# SSTuino_Evo.net
KiCad netlist of a schematic drawn in EAGLE
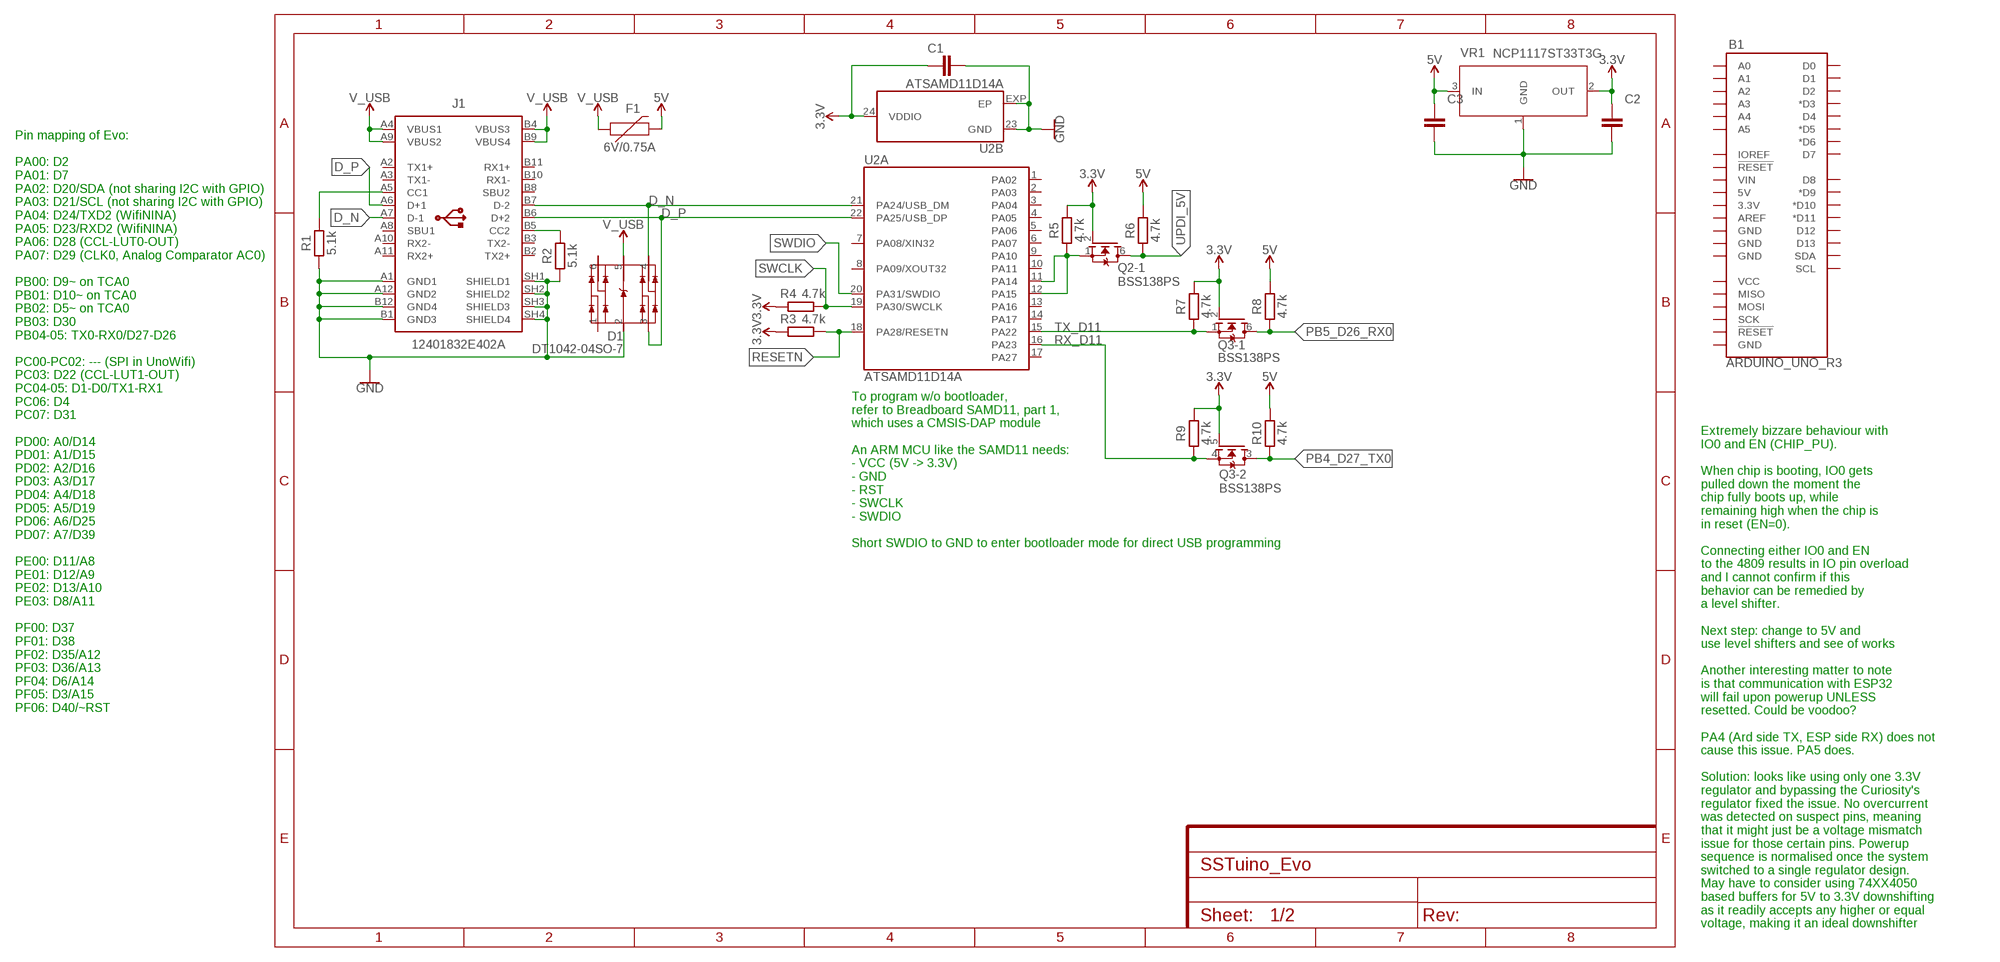
[diagram p0: schematic, sheet 1]
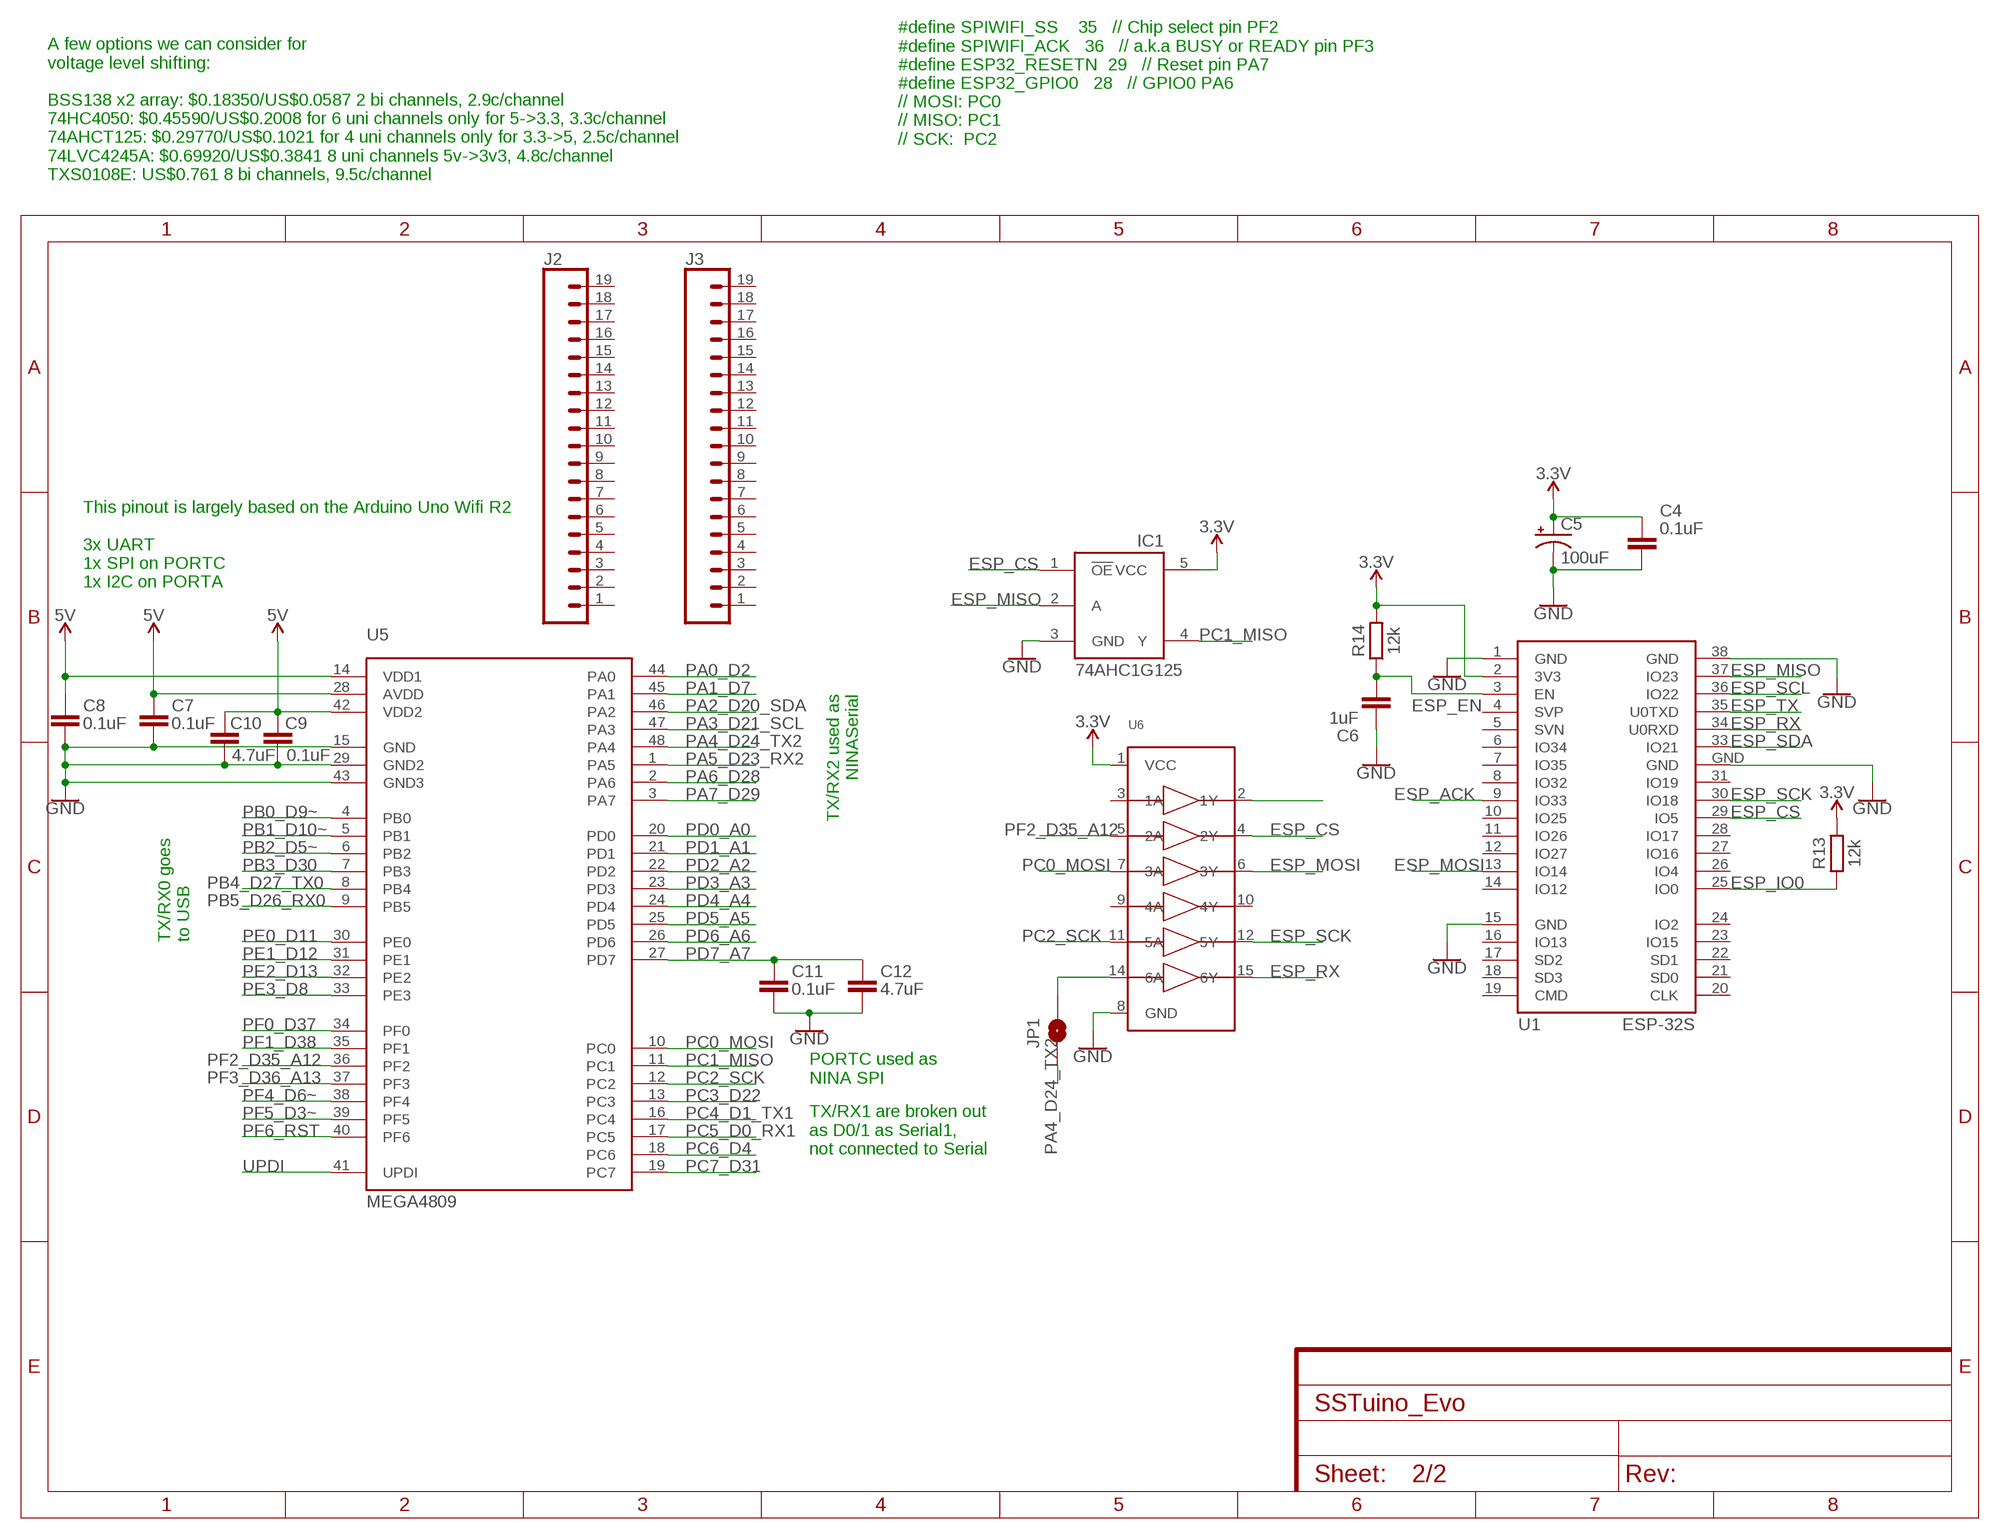
[diagram p1: schematic, sheet 2]

(export (version "E")
  (design (tool "Eeschema 10.0.6"))
  (components
    (comp (ref "C4")
      (value "0.1uF")
      (footprint "eagle-import:CAPC1005X60")
      (libsource (lib "eagle-import") (part "CCHIP-0402(1005-METRIC)_"))
    )
    (comp (ref "C5")
      (value "100uF")
      (footprint "eagle-import:CAPMP3216X180N")
      (libsource (lib "eagle-import") (part "C-POL-USTANTALUM-1206(3216-METRIC)_"))
    )
    (comp (ref "C6")
      (value "1uF")
      (footprint "eagle-import:CAPC1005X60")
      (libsource (lib "eagle-import") (part "CCHIP-0402(1005-METRIC)_"))
    )
    (comp (ref "C7")
      (value "0.1uF")
      (footprint "eagle-import:CAPC1005X60")
      (libsource (lib "eagle-import") (part "CCHIP-0402(1005-METRIC)_"))
    )
    (comp (ref "C8")
      (value "0.1uF")
      (footprint "eagle-import:CAPC1005X60")
      (libsource (lib "eagle-import") (part "CCHIP-0402(1005-METRIC)_"))
    )
    (comp (ref "C9")
      (value "0.1uF")
      (footprint "eagle-import:CAPC1005X60")
      (libsource (lib "eagle-import") (part "CCHIP-0402(1005-METRIC)_"))
    )
    (comp (ref "C10")
      (value "4.7uF")
      (footprint "eagle-import:CAPC1005X60")
      (libsource (lib "eagle-import") (part "CCHIP-0402(1005-METRIC)_"))
    )
    (comp (ref "C11")
      (value "0.1uF")
      (footprint "eagle-import:CAPC1005X60")
      (libsource (lib "eagle-import") (part "CCHIP-0402(1005-METRIC)_"))
    )
    (comp (ref "C12")
      (value "4.7uF")
      (footprint "eagle-import:CAPC1005X60")
      (libsource (lib "eagle-import") (part "CCHIP-0402(1005-METRIC)_"))
    )
    (comp (ref "IC1")
      (value "74AHC1G125")
      (footprint "eagle-import:SOT23-5L")
      (libsource (lib "eagle-import") (part "74AHC1G125"))
    )
    (comp (ref "J2")
      (value "CONN_191X19_NO_SILK")
      (footprint "eagle-import:1X19_NO_SILK")
      (libsource (lib "eagle-import") (part "CONN_191X19_NO_SILK"))
    )
    (comp (ref "J3")
      (value "CONN_191X19_NO_SILK")
      (footprint "eagle-import:1X19_NO_SILK")
      (libsource (lib "eagle-import") (part "CONN_191X19_NO_SILK"))
    )
    (comp (ref "JP1")
      (value "JUMPER-SMT_2_NO_SILK")
      (footprint "eagle-import:SMT-JUMPER_2_NO_SILK")
      (libsource (lib "eagle-import") (part "JUMPER-SMT_2_NO_SILK"))
    )
    (comp (ref "R13")
      (value "12k")
      (footprint "eagle-import:RESC1005X40")
      (libsource (lib "eagle-import") (part "RCHIP-0402(1005-METRIC)_"))
    )
    (comp (ref "R14")
      (value "12k")
      (footprint "eagle-import:RESC1005X40")
      (libsource (lib "eagle-import") (part "RCHIP-0402(1005-METRIC)_"))
    )
    (comp (ref "U1")
      (value "ESP-32S")
      (footprint "eagle-import:ESP-32S")
      (libsource (lib "eagle-import") (part "ESP-32S"))
    )
    (comp (ref "U5")
      (value "MEGA4809")
      (footprint "eagle-import:TQFP48")
      (libsource (lib "eagle-import") (part "MEGA4809"))
    )
    (comp (ref "U6")
      (value "74HC4050DTSSOP")
      (footprint "eagle-import:TSSOP16")
      (libsource (lib "eagle-import") (part "74HC4050DTSSOP"))
    )
    (comp (ref "B1")
      (value "ARDUINO_UNO_R3")
      (footprint "eagle-import:ARDUINO_R3")
      (libsource (lib "eagle-import") (part "ARDUINO_UNO_R3"))
    )
    (comp (ref "C1")
      (value "100n")
      (footprint "eagle-import:CAPC1005X60")
      (libsource (lib "eagle-import") (part "CCHIP-0402(1005-METRIC)_"))
    )
    (comp (ref "C2")
      (value "10uF")
      (footprint "eagle-import:CAPC1608X85")
      (libsource (lib "eagle-import") (part "CCHIP-0603(1608-METRIC)_"))
    )
    (comp (ref "C3")
      (value "10uF")
      (footprint "eagle-import:CAPC1608X85")
      (libsource (lib "eagle-import") (part "CCHIP-0603(1608-METRIC)_"))
    )
    (comp (ref "D1")
      (value "DT1042-04SO-7")
      (footprint "eagle-import:SOT95P285X140-6N")
      (fields (field (name "DIGI-KEY_PART_NUMBER") "DT1042-04SO-7DICT-ND") (field (name "MF") "Diodes Inc."))
      (libsource (lib "eagle-import") (part "DT1042-04SO-7"))
    )
    (comp (ref "F1")
      (value "6V/0.75A")
      (footprint "eagle-import:1206")
      (libsource (lib "eagle-import") (part "PPTC_THREE-QUARTER-AMP"))
    )
    (comp (ref "J1")
      (value "12401832E402A")
      (footprint "eagle-import:12401832E402A")
      (fields (field (name "MANUFACTURER") "Amphenol ICC"))
      (libsource (lib "eagle-import") (part "12401832E402A"))
    )
    (comp (ref "Q2")
      (value "BSS138PS")
      (footprint "eagle-import:ARDUINO-TRANSISTORS_SOT363")
      (fields (field (name "MANUFACTURER") "NXP"))
      (libsource (lib "eagle-import") (part "BSS138PS"))
    )
    (comp (ref "Q3")
      (value "BSS138PS")
      (footprint "eagle-import:ARDUINO-TRANSISTORS_SOT363")
      (fields (field (name "MANUFACTURER") "NXP"))
      (libsource (lib "eagle-import") (part "BSS138PS"))
    )
    (comp (ref "R1")
      (value "5.1k")
      (footprint "eagle-import:RESC1005X40")
      (libsource (lib "eagle-import") (part "RCHIP-0402(1005-METRIC)_"))
    )
    (comp (ref "R2")
      (value "5.1k")
      (footprint "eagle-import:RESC1005X40")
      (libsource (lib "eagle-import") (part "RCHIP-0402(1005-METRIC)_"))
    )
    (comp (ref "R3")
      (value "4.7k")
      (footprint "eagle-import:RESC1005X40")
      (libsource (lib "eagle-import") (part "RCHIP-0402(1005-METRIC)_"))
    )
    (comp (ref "R4")
      (value "4.7k")
      (footprint "eagle-import:RESC1005X40")
      (libsource (lib "eagle-import") (part "RCHIP-0402(1005-METRIC)_"))
    )
    (comp (ref "R5")
      (value "4.7k")
      (footprint "eagle-import:RESC1005X40")
      (libsource (lib "eagle-import") (part "RCHIP-0402(1005-METRIC)_"))
    )
    (comp (ref "R6")
      (value "4.7k")
      (footprint "eagle-import:RESC1005X40")
      (libsource (lib "eagle-import") (part "RCHIP-0402(1005-METRIC)_"))
    )
    (comp (ref "R7")
      (value "4.7k")
      (footprint "eagle-import:RESC1005X40")
      (libsource (lib "eagle-import") (part "RCHIP-0402(1005-METRIC)_"))
    )
    (comp (ref "R8")
      (value "4.7k")
      (footprint "eagle-import:RESC1005X40")
      (libsource (lib "eagle-import") (part "RCHIP-0402(1005-METRIC)_"))
    )
    (comp (ref "R9")
      (value "4.7k")
      (footprint "eagle-import:RESC1005X40")
      (libsource (lib "eagle-import") (part "RCHIP-0402(1005-METRIC)_"))
    )
    (comp (ref "R10")
      (value "4.7k")
      (footprint "eagle-import:RESC1005X40")
      (libsource (lib "eagle-import") (part "RCHIP-0402(1005-METRIC)_"))
    )
    (comp (ref "U2")
      (value "ATSAMD11D14A")
      (footprint "eagle-import:ARDUINO-UCS&SOCS_HVQFN24")
      (fields (field (name "MANUFACTURER") "Microchip"))
      (libsource (lib "eagle-import") (part "ATSAMD11D14"))
    )
    (comp (ref "VR1")
      (value "NCP1117ST33T3G")
      (footprint "eagle-import:SOT230P700X170-4")
      (fields (field (name "MANUFACTURER") "ON Semiconductor"))
      (libsource (lib "eagle-import") (part "NCP1117ST33T3GSOT-223"))
    )
  )
  (nets
    (net (code "1") (name "3.3V") (class "Default")
      (node (ref "C1") (pin "1") (pinfunction "1_1") (pintype "passive"))
      (node (ref "C2") (pin "1") (pinfunction "1_1") (pintype "passive"))
      (node (ref "C4") (pin "1") (pinfunction "1_1") (pintype "passive"))
      (node (ref "C5") (pin "1") (pinfunction "+_1") (pintype "passive"))
      (node (ref "IC1") (pin "5") (pinfunction "VCC_5") (pintype "power_in"))
      (node (ref "Q2") (pin "2") (pinfunction "G_2") (pintype "passive"))
      (node (ref "Q3") (pin "2") (pinfunction "G_2") (pintype "passive"))
      (node (ref "Q3") (pin "5") (pinfunction "G_5") (pintype "passive"))
      (node (ref "R13") (pin "2") (pinfunction "2_2") (pintype "passive"))
      (node (ref "R14") (pin "2") (pinfunction "2_2") (pintype "passive"))
      (node (ref "R3") (pin "2") (pinfunction "2_2") (pintype "passive"))
      (node (ref "R4") (pin "2") (pinfunction "2_2") (pintype "passive"))
      (node (ref "R5") (pin "2") (pinfunction "2_2") (pintype "passive"))
      (node (ref "R7") (pin "2") (pinfunction "2_2") (pintype "passive"))
      (node (ref "R9") (pin "2") (pinfunction "2_2") (pintype "passive"))
      (node (ref "U1") (pin "2") (pinfunction "3V3_2") (pintype "power_in"))
      (node (ref "U2") (pin "24") (pinfunction "VDDIO_24") (pintype "power_in"))
      (node (ref "U6") (pin "1") (pinfunction "VCC_1") (pintype "bidirectional"))
      (node (ref "VR1") (pin "2") (pinfunction "OUT_2") (pintype "output"))
    )
    (net (code "2") (name "5V") (class "Default")
      (node (ref "C10") (pin "1") (pinfunction "1_1") (pintype "passive"))
      (node (ref "C3") (pin "1") (pinfunction "1_1") (pintype "passive"))
      (node (ref "C7") (pin "1") (pinfunction "1_1") (pintype "passive"))
      (node (ref "C8") (pin "1") (pinfunction "1_1") (pintype "passive"))
      (node (ref "C9") (pin "1") (pinfunction "1_1") (pintype "passive"))
      (node (ref "F1") (pin "2") (pinfunction "2_2") (pintype "bidirectional"))
      (node (ref "R10") (pin "2") (pinfunction "2_2") (pintype "passive"))
      (node (ref "R6") (pin "2") (pinfunction "2_2") (pintype "passive"))
      (node (ref "R8") (pin "2") (pinfunction "2_2") (pintype "passive"))
      (node (ref "U5") (pin "14") (pinfunction "VDD1_14") (pintype "bidirectional"))
      (node (ref "U5") (pin "28") (pinfunction "AVDD_28") (pintype "bidirectional"))
      (node (ref "U5") (pin "42") (pinfunction "VDD2_42") (pintype "bidirectional"))
      (node (ref "VR1") (pin "3") (pinfunction "IN_3") (pintype "input"))
    )
    (net (code "3") (name "D_N") (class "Default")
      (node (ref "D1") (pin "4") (pinfunction "IO3_4") (pintype "passive"))
      (node (ref "J1") (pin "A7") (pinfunction "D-1_A7") (pintype "bidirectional"))
      (node (ref "J1") (pin "B7") (pinfunction "D-2_B7") (pintype "bidirectional"))
      (node (ref "U2") (pin "21") (pinfunction "PA24/USB_DM_21") (pintype "bidirectional"))
    )
    (net (code "4") (name "D_P") (class "Default")
      (node (ref "D1") (pin "3") (pinfunction "IO2_3") (pintype "passive"))
      (node (ref "J1") (pin "A6") (pinfunction "D+1_A6") (pintype "bidirectional"))
      (node (ref "J1") (pin "B6") (pinfunction "D+2_B6") (pintype "bidirectional"))
      (node (ref "U2") (pin "22") (pinfunction "PA25/USB_DP_22") (pintype "bidirectional"))
    )
    (net (code "5") (name "ESP_ACK") (class "Default")
      (node (ref "U1") (pin "9") (pinfunction "IO33_9") (pintype "bidirectional"))
    )
    (net (code "6") (name "ESP_CS") (class "Default")
      (node (ref "IC1") (pin "1") (pinfunction "~{OE}_1") (pintype "input"))
      (node (ref "U1") (pin "29") (pinfunction "IO5_29") (pintype "bidirectional"))
      (node (ref "U6") (pin "4") (pinfunction "2Y_4") (pintype "bidirectional"))
    )
    (net (code "7") (name "ESP_EN") (class "Default")
      (node (ref "C6") (pin "2") (pinfunction "2_2") (pintype "passive"))
      (node (ref "R14") (pin "1") (pinfunction "1_1") (pintype "passive"))
      (node (ref "U1") (pin "3") (pinfunction "EN_3") (pintype "input"))
    )
    (net (code "8") (name "ESP_IO0") (class "Default")
      (node (ref "R13") (pin "1") (pinfunction "1_1") (pintype "passive"))
      (node (ref "U1") (pin "25") (pinfunction "IO0_25") (pintype "bidirectional"))
    )
    (net (code "9") (name "ESP_MISO") (class "Default")
      (node (ref "IC1") (pin "2") (pinfunction "A_2") (pintype "input"))
      (node (ref "U1") (pin "37") (pinfunction "IO23_37") (pintype "bidirectional"))
    )
    (net (code "10") (name "ESP_MOSI") (class "Default")
      (node (ref "U1") (pin "13") (pinfunction "IO14_13") (pintype "bidirectional"))
      (node (ref "U6") (pin "6") (pinfunction "3Y_6") (pintype "bidirectional"))
    )
    (net (code "11") (name "ESP_RX") (class "Default")
      (node (ref "U1") (pin "34") (pinfunction "U0RXD_34") (pintype "bidirectional"))
      (node (ref "U6") (pin "15") (pinfunction "6Y_15") (pintype "bidirectional"))
    )
    (net (code "12") (name "ESP_SCK") (class "Default")
      (node (ref "U1") (pin "30") (pinfunction "IO18_30") (pintype "bidirectional"))
      (node (ref "U6") (pin "12") (pinfunction "5Y_12") (pintype "bidirectional"))
    )
    (net (code "13") (name "ESP_SCL") (class "Default")
      (node (ref "U1") (pin "36") (pinfunction "IO22_36") (pintype "bidirectional"))
    )
    (net (code "14") (name "ESP_SDA") (class "Default")
      (node (ref "U1") (pin "33") (pinfunction "IO21_33") (pintype "bidirectional"))
    )
    (net (code "15") (name "ESP_TX") (class "Default")
      (node (ref "U1") (pin "35") (pinfunction "U0TXD_35") (pintype "bidirectional"))
    )
    (net (code "16") (name "GND") (class "Default")
      (node (ref "C1") (pin "2") (pinfunction "2_2") (pintype "passive"))
      (node (ref "C10") (pin "2") (pinfunction "2_2") (pintype "passive"))
      (node (ref "C11") (pin "2") (pinfunction "2_2") (pintype "passive"))
      (node (ref "C12") (pin "2") (pinfunction "2_2") (pintype "passive"))
      (node (ref "C2") (pin "2") (pinfunction "2_2") (pintype "passive"))
      (node (ref "C3") (pin "2") (pinfunction "2_2") (pintype "passive"))
      (node (ref "C4") (pin "2") (pinfunction "2_2") (pintype "passive"))
      (node (ref "C5") (pin "2") (pinfunction "-_2") (pintype "passive"))
      (node (ref "C6") (pin "1") (pinfunction "1_1") (pintype "passive"))
      (node (ref "C7") (pin "2") (pinfunction "2_2") (pintype "passive"))
      (node (ref "C8") (pin "2") (pinfunction "2_2") (pintype "passive"))
      (node (ref "C9") (pin "2") (pinfunction "2_2") (pintype "passive"))
      (node (ref "D1") (pin "2") (pinfunction "VSS_2") (pintype "power_in"))
      (node (ref "IC1") (pin "3") (pinfunction "GND_3") (pintype "power_in"))
      (node (ref "J1") (pin "A1") (pinfunction "GND1_A1") (pintype "power_in"))
      (node (ref "J1") (pin "A12") (pinfunction "GND2_A12") (pintype "power_in"))
      (node (ref "J1") (pin "B1") (pinfunction "GND3_B1") (pintype "power_in"))
      (node (ref "J1") (pin "B12") (pinfunction "GND4_B12") (pintype "power_in"))
      (node (ref "J1") (pin "SH1") (pinfunction "SHIELD1_SH1") (pintype "power_in"))
      (node (ref "J1") (pin "SH2") (pinfunction "SHIELD2_SH2") (pintype "power_in"))
      (node (ref "J1") (pin "SH3") (pinfunction "SHIELD3_SH3") (pintype "power_in"))
      (node (ref "J1") (pin "SH4") (pinfunction "SHIELD4_SH4") (pintype "power_in"))
      (node (ref "R1") (pin "1") (pinfunction "1_1") (pintype "passive"))
      (node (ref "R2") (pin "1") (pinfunction "1_1") (pintype "passive"))
      (node (ref "U1") (pin "1") (pinfunction "GND_1") (pintype "power_in"))
      (node (ref "U1") (pin "15") (pinfunction "GND_15") (pintype "power_in"))
      (node (ref "U1") (pin "38") (pinfunction "GND_38") (pintype "power_in"))
      (node (ref "U1") (pin "GND") (pinfunction "GND_GND") (pintype "power_in"))
      (node (ref "U2") (pin "23") (pinfunction "GND_23") (pintype "power_in"))
      (node (ref "U2") (pin "EXP") (pinfunction "EP_EXP") (pintype "power_in"))
      (node (ref "U5") (pin "15") (pinfunction "GND_15") (pintype "bidirectional"))
      (node (ref "U5") (pin "29") (pinfunction "GND2_29") (pintype "bidirectional"))
      (node (ref "U5") (pin "43") (pinfunction "GND3_43") (pintype "bidirectional"))
      (node (ref "U6") (pin "8") (pinfunction "GND_8") (pintype "bidirectional"))
      (node (ref "VR1") (pin "1") (pinfunction "GND_1") (pintype "passive"))
    )
    (net (code "17") (name "Net-(J1-CC1)") (class "Default")
      (node (ref "J1") (pin "A5") (pinfunction "CC1_A5") (pintype "bidirectional"))
      (node (ref "R1") (pin "2") (pinfunction "2_2") (pintype "passive"))
    )
    (net (code "18") (name "Net-(J1-CC2)") (class "Default")
      (node (ref "J1") (pin "B5") (pinfunction "CC2_B5") (pintype "bidirectional"))
      (node (ref "R2") (pin "2") (pinfunction "2_2") (pintype "passive"))
    )
    (net (code "19") (name "Net-(Q2A-S)") (class "Default")
      (node (ref "Q2") (pin "1") (pinfunction "S_1") (pintype "passive"))
      (node (ref "R5") (pin "1") (pinfunction "1_1") (pintype "passive"))
      (node (ref "U2") (pin "11") (pinfunction "PA14_11") (pintype "bidirectional"))
      (node (ref "U2") (pin "12") (pinfunction "PA15_12") (pintype "bidirectional"))
    )
    (net (code "20") (name "Net-(U6-6A)") (class "Default")
      (node (ref "JP1") (pin "2") (pinfunction "2_2") (pintype "passive"))
      (node (ref "U6") (pin "14") (pinfunction "6A_14") (pintype "bidirectional"))
    )
    (net (code "21") (name "PA0_D2") (class "Default")
      (node (ref "U5") (pin "44") (pinfunction "PA0_44") (pintype "bidirectional"))
    )
    (net (code "22") (name "PA1_D7") (class "Default")
      (node (ref "U5") (pin "45") (pinfunction "PA1_45") (pintype "bidirectional"))
    )
    (net (code "23") (name "PA2_D20_SDA") (class "Default")
      (node (ref "U5") (pin "46") (pinfunction "PA2_46") (pintype "bidirectional"))
    )
    (net (code "24") (name "PA3_D21_SCL") (class "Default")
      (node (ref "U5") (pin "47") (pinfunction "PA3_47") (pintype "bidirectional"))
    )
    (net (code "25") (name "PA4_D24_TX2") (class "Default")
      (node (ref "JP1") (pin "1") (pinfunction "1_1") (pintype "passive"))
      (node (ref "U5") (pin "48") (pinfunction "PA4_48") (pintype "bidirectional"))
    )
    (net (code "26") (name "PA5_D23_RX2") (class "Default")
      (node (ref "U5") (pin "1") (pinfunction "PA5_1") (pintype "bidirectional"))
    )
    (net (code "27") (name "PA6_D28") (class "Default")
      (node (ref "U5") (pin "2") (pinfunction "PA6_2") (pintype "bidirectional"))
    )
    (net (code "28") (name "PA7_D29") (class "Default")
      (node (ref "U5") (pin "3") (pinfunction "PA7_3") (pintype "bidirectional"))
    )
    (net (code "29") (name "PB0_D9~{}") (class "Default")
      (node (ref "U5") (pin "4") (pinfunction "PB0_4") (pintype "bidirectional"))
    )
    (net (code "30") (name "PB1_D10~{}") (class "Default")
      (node (ref "U5") (pin "5") (pinfunction "PB1_5") (pintype "bidirectional"))
    )
    (net (code "31") (name "PB2_D5~{}") (class "Default")
      (node (ref "U5") (pin "6") (pinfunction "PB2_6") (pintype "bidirectional"))
    )
    (net (code "32") (name "PB3_D30") (class "Default")
      (node (ref "U5") (pin "7") (pinfunction "PB3_7") (pintype "bidirectional"))
    )
    (net (code "33") (name "PB4_D27_TX0") (class "Default")
      (node (ref "Q3") (pin "3") (pinfunction "D_3") (pintype "passive"))
      (node (ref "R10") (pin "1") (pinfunction "1_1") (pintype "passive"))
      (node (ref "U5") (pin "8") (pinfunction "PB4_8") (pintype "bidirectional"))
    )
    (net (code "34") (name "PB5_D26_RX0") (class "Default")
      (node (ref "Q3") (pin "6") (pinfunction "D_6") (pintype "passive"))
      (node (ref "R8") (pin "1") (pinfunction "1_1") (pintype "passive"))
      (node (ref "U5") (pin "9") (pinfunction "PB5_9") (pintype "bidirectional"))
    )
    (net (code "35") (name "PC0_MOSI") (class "Default")
      (node (ref "U5") (pin "10") (pinfunction "PC0_10") (pintype "bidirectional"))
      (node (ref "U6") (pin "7") (pinfunction "3A_7") (pintype "bidirectional"))
    )
    (net (code "36") (name "PC1_MISO") (class "Default")
      (node (ref "IC1") (pin "4") (pinfunction "Y_4") (pintype "output"))
      (node (ref "U5") (pin "11") (pinfunction "PC1_11") (pintype "bidirectional"))
    )
    (net (code "37") (name "PC2_SCK") (class "Default")
      (node (ref "U5") (pin "12") (pinfunction "PC2_12") (pintype "bidirectional"))
      (node (ref "U6") (pin "11") (pinfunction "5A_11") (pintype "bidirectional"))
    )
    (net (code "38") (name "PC3_D22") (class "Default")
      (node (ref "U5") (pin "13") (pinfunction "PC3_13") (pintype "bidirectional"))
    )
    (net (code "39") (name "PC4_D1_TX1") (class "Default")
      (node (ref "U5") (pin "16") (pinfunction "PC4_16") (pintype "bidirectional"))
    )
    (net (code "40") (name "PC5_D0_RX1") (class "Default")
      (node (ref "U5") (pin "17") (pinfunction "PC5_17") (pintype "bidirectional"))
    )
    (net (code "41") (name "PC6_D4") (class "Default")
      (node (ref "U5") (pin "18") (pinfunction "PC6_18") (pintype "bidirectional"))
    )
    (net (code "42") (name "PC7_D31") (class "Default")
      (node (ref "U5") (pin "19") (pinfunction "PC7_19") (pintype "bidirectional"))
    )
    (net (code "43") (name "PD0_A0") (class "Default")
      (node (ref "U5") (pin "20") (pinfunction "PD0_20") (pintype "bidirectional"))
    )
    (net (code "44") (name "PD1_A1") (class "Default")
      (node (ref "U5") (pin "21") (pinfunction "PD1_21") (pintype "bidirectional"))
    )
    (net (code "45") (name "PD2_A2") (class "Default")
      (node (ref "U5") (pin "22") (pinfunction "PD2_22") (pintype "bidirectional"))
    )
    (net (code "46") (name "PD3_A3") (class "Default")
      (node (ref "U5") (pin "23") (pinfunction "PD3_23") (pintype "bidirectional"))
    )
    (net (code "47") (name "PD4_A4") (class "Default")
      (node (ref "U5") (pin "24") (pinfunction "PD4_24") (pintype "bidirectional"))
    )
    (net (code "48") (name "PD5_A5") (class "Default")
      (node (ref "U5") (pin "25") (pinfunction "PD5_25") (pintype "bidirectional"))
    )
    (net (code "49") (name "PD6_A6") (class "Default")
      (node (ref "U5") (pin "26") (pinfunction "PD6_26") (pintype "bidirectional"))
    )
    (net (code "50") (name "PD7_A7") (class "Default")
      (node (ref "C11") (pin "1") (pinfunction "1_1") (pintype "passive"))
      (node (ref "C12") (pin "1") (pinfunction "1_1") (pintype "passive"))
      (node (ref "U5") (pin "27") (pinfunction "PD7_27") (pintype "bidirectional"))
    )
    (net (code "51") (name "PE0_D11") (class "Default")
      (node (ref "U5") (pin "30") (pinfunction "PE0_30") (pintype "bidirectional"))
    )
    (net (code "52") (name "PE1_D12") (class "Default")
      (node (ref "U5") (pin "31") (pinfunction "PE1_31") (pintype "bidirectional"))
    )
    (net (code "53") (name "PE2_D13") (class "Default")
      (node (ref "U5") (pin "32") (pinfunction "PE2_32") (pintype "bidirectional"))
    )
    (net (code "54") (name "PE3_D8") (class "Default")
      (node (ref "U5") (pin "33") (pinfunction "PE3_33") (pintype "bidirectional"))
    )
    (net (code "55") (name "PF0_D37") (class "Default")
      (node (ref "U5") (pin "34") (pinfunction "PF0_34") (pintype "bidirectional"))
    )
    (net (code "56") (name "PF1_D38") (class "Default")
      (node (ref "U5") (pin "35") (pinfunction "PF1_35") (pintype "bidirectional"))
    )
    (net (code "57") (name "PF2_D35_A12") (class "Default")
      (node (ref "U5") (pin "36") (pinfunction "PF2_36") (pintype "bidirectional"))
      (node (ref "U6") (pin "5") (pinfunction "2A_5") (pintype "bidirectional"))
    )
    (net (code "58") (name "PF3_D36_A13") (class "Default")
      (node (ref "U5") (pin "37") (pinfunction "PF3_37") (pintype "bidirectional"))
    )
    (net (code "59") (name "PF4_D6~{}") (class "Default")
      (node (ref "U5") (pin "38") (pinfunction "PF4_38") (pintype "bidirectional"))
    )
    (net (code "60") (name "PF5_D3~{}") (class "Default")
      (node (ref "U5") (pin "39") (pinfunction "PF5_39") (pintype "bidirectional"))
    )
    (net (code "61") (name "PF6_RST") (class "Default")
      (node (ref "U5") (pin "40") (pinfunction "PF6_40") (pintype "bidirectional"))
    )
    (net (code "62") (name "RESETN") (class "Default")
      (node (ref "R3") (pin "1") (pinfunction "1_1") (pintype "passive"))
      (node (ref "U2") (pin "18") (pinfunction "PA28/RESETN_18") (pintype "bidirectional"))
    )
    (net (code "63") (name "RX_D11") (class "Default")
      (node (ref "Q3") (pin "4") (pinfunction "S_4") (pintype "passive"))
      (node (ref "R9") (pin "1") (pinfunction "1_1") (pintype "passive"))
      (node (ref "U2") (pin "16") (pinfunction "PA23_16") (pintype "bidirectional"))
    )
    (net (code "64") (name "SWCLK") (class "Default")
      (node (ref "R4") (pin "1") (pinfunction "1_1") (pintype "passive"))
      (node (ref "U2") (pin "19") (pinfunction "PA30/SWCLK_19") (pintype "bidirectional"))
    )
    (net (code "65") (name "SWDIO") (class "Default")
      (node (ref "U2") (pin "20") (pinfunction "PA31/SWDIO_20") (pintype "bidirectional"))
    )
    (net (code "66") (name "TX_D11") (class "Default")
      (node (ref "Q3") (pin "1") (pinfunction "S_1") (pintype "passive"))
      (node (ref "R7") (pin "1") (pinfunction "1_1") (pintype "passive"))
      (node (ref "U2") (pin "15") (pinfunction "PA22_15") (pintype "bidirectional"))
    )
    (net (code "67") (name "UPDI") (class "Default")
      (node (ref "U5") (pin "41") (pinfunction "UPDI_41") (pintype "bidirectional"))
    )
    (net (code "68") (name "UPDI_5V") (class "Default")
      (node (ref "Q2") (pin "6") (pinfunction "D_6") (pintype "passive"))
      (node (ref "R6") (pin "1") (pinfunction "1_1") (pintype "passive"))
    )
    (net (code "69") (name "V_USB") (class "Default")
      (node (ref "D1") (pin "5") (pinfunction "VCC_5") (pintype "power_in"))
      (node (ref "F1") (pin "1") (pinfunction "1_1") (pintype "bidirectional"))
      (node (ref "J1") (pin "A4") (pinfunction "VBUS1_A4") (pintype "power_in"))
      (node (ref "J1") (pin "A9") (pinfunction "VBUS2_A9") (pintype "power_in"))
      (node (ref "J1") (pin "B4") (pinfunction "VBUS3_B4") (pintype "power_in"))
      (node (ref "J1") (pin "B9") (pinfunction "VBUS4_B9") (pintype "power_in"))
    )
    (net (code "70") (name "unconnected-(B1-*D3-PadD3)") (class "Default")
      (node (ref "B1") (pin "D3") (pinfunction "*D3_D3") (pintype "bidirectional"))
    )
    (net (code "71") (name "unconnected-(B1-*D5-PadD5)") (class "Default")
      (node (ref "B1") (pin "D5") (pinfunction "*D5_D5") (pintype "bidirectional"))
    )
    (net (code "72") (name "unconnected-(B1-*D6-PadD6)") (class "Default")
      (node (ref "B1") (pin "D6") (pinfunction "*D6_D6") (pintype "bidirectional"))
    )
    (net (code "73") (name "unconnected-(B1-*D9-PadD9)") (class "Default")
      (node (ref "B1") (pin "D9") (pinfunction "*D9_D9") (pintype "bidirectional"))
    )
    (net (code "74") (name "unconnected-(B1-*D10-PadD10)") (class "Default")
      (node (ref "B1") (pin "D10") (pinfunction "*D10_D10") (pintype "bidirectional"))
    )
    (net (code "75") (name "unconnected-(B1-*D11-PadD11)") (class "Default")
      (node (ref "B1") (pin "D11") (pinfunction "*D11_D11") (pintype "bidirectional"))
    )
    (net (code "76") (name "unconnected-(B1-GND-PadGND@1)") (class "Default")
      (node (ref "B1") (pin "GND@1") (pinfunction "GND_GND@1") (pintype "bidirectional"))
    )
    (net (code "77") (name "unconnected-(B1-GND-PadGND@2)") (class "Default")
      (node (ref "B1") (pin "GND@2") (pinfunction "GND_GND@2") (pintype "bidirectional"))
    )
    (net (code "78") (name "unconnected-(B1-GND-PadGND@3)") (class "Default")
      (node (ref "B1") (pin "GND@3") (pinfunction "GND_GND@3") (pintype "bidirectional"))
    )
    (net (code "79") (name "unconnected-(B1-GND-PadGND@4)") (class "Default")
      (node (ref "B1") (pin "GND@4") (pinfunction "GND_GND@4") (pintype "bidirectional"))
    )
    (net (code "80") (name "unconnected-(B1-Pad3.3V)") (class "Default")
      (node (ref "B1") (pin "3.3V") (pinfunction "3.3V_3.3V") (pintype "bidirectional"))
    )
    (net (code "81") (name "unconnected-(B1-Pad5V)") (class "Default")
      (node (ref "B1") (pin "5V") (pinfunction "5V_5V") (pintype "bidirectional"))
    )
    (net (code "82") (name "unconnected-(B1-PadA0)") (class "Default")
      (node (ref "B1") (pin "A0") (pinfunction "A0_A0") (pintype "bidirectional"))
    )
    (net (code "83") (name "unconnected-(B1-PadA1)") (class "Default")
      (node (ref "B1") (pin "A1") (pinfunction "A1_A1") (pintype "bidirectional"))
    )
    (net (code "84") (name "unconnected-(B1-PadA2)") (class "Default")
      (node (ref "B1") (pin "A2") (pinfunction "A2_A2") (pintype "bidirectional"))
    )
    (net (code "85") (name "unconnected-(B1-PadA3)") (class "Default")
      (node (ref "B1") (pin "A3") (pinfunction "A3_A3") (pintype "bidirectional"))
    )
    (net (code "86") (name "unconnected-(B1-PadA4)") (class "Default")
      (node (ref "B1") (pin "A4") (pinfunction "A4_A4") (pintype "bidirectional"))
    )
    (net (code "87") (name "unconnected-(B1-PadA5)") (class "Default")
      (node (ref "B1") (pin "A5") (pinfunction "A5_A5") (pintype "bidirectional"))
    )
    (net (code "88") (name "unconnected-(B1-PadAREF)") (class "Default")
      (node (ref "B1") (pin "AREF") (pinfunction "AREF_AREF") (pintype "bidirectional"))
    )
    (net (code "89") (name "unconnected-(B1-PadD0)") (class "Default")
      (node (ref "B1") (pin "D0") (pinfunction "D0_D0") (pintype "bidirectional"))
    )
    (net (code "90") (name "unconnected-(B1-PadD1)") (class "Default")
      (node (ref "B1") (pin "D1") (pinfunction "D1_D1") (pintype "bidirectional"))
    )
    (net (code "91") (name "unconnected-(B1-PadD2)") (class "Default")
      (node (ref "B1") (pin "D2") (pinfunction "D2_D2") (pintype "bidirectional"))
    )
    (net (code "92") (name "unconnected-(B1-PadD4)") (class "Default")
      (node (ref "B1") (pin "D4") (pinfunction "D4_D4") (pintype "bidirectional"))
    )
    (net (code "93") (name "unconnected-(B1-PadD7)") (class "Default")
      (node (ref "B1") (pin "D7") (pinfunction "D7_D7") (pintype "bidirectional"))
    )
    (net (code "94") (name "unconnected-(B1-PadD8)") (class "Default")
      (node (ref "B1") (pin "D8") (pinfunction "D8_D8") (pintype "bidirectional"))
    )
    (net (code "95") (name "unconnected-(B1-PadD12)") (class "Default")
      (node (ref "B1") (pin "D12") (pinfunction "D12_D12") (pintype "bidirectional"))
    )
    (net (code "96") (name "unconnected-(B1-PadD13)") (class "Default")
      (node (ref "B1") (pin "D13") (pinfunction "D13_D13") (pintype "bidirectional"))
    )
    (net (code "97") (name "unconnected-(B1-PadIOREF)") (class "Default")
      (node (ref "B1") (pin "IOREF") (pinfunction "IOREF_IOREF") (pintype "bidirectional"))
    )
    (net (code "98") (name "unconnected-(B1-PadMISO)") (class "Default")
      (node (ref "B1") (pin "MISO") (pinfunction "MISO_MISO") (pintype "bidirectional"))
    )
    (net (code "99") (name "unconnected-(B1-PadMOSI)") (class "Default")
      (node (ref "B1") (pin "MOSI") (pinfunction "MOSI_MOSI") (pintype "bidirectional"))
    )
    (net (code "100") (name "unconnected-(B1-PadSCK)") (class "Default")
      (node (ref "B1") (pin "SCK") (pinfunction "SCK_SCK") (pintype "bidirectional"))
    )
    (net (code "101") (name "unconnected-(B1-PadSCL)") (class "Default")
      (node (ref "B1") (pin "SCL") (pinfunction "SCL_SCL") (pintype "bidirectional"))
    )
    (net (code "102") (name "unconnected-(B1-PadSDA)") (class "Default")
      (node (ref "B1") (pin "SDA") (pinfunction "SDA_SDA") (pintype "bidirectional"))
    )
    (net (code "103") (name "unconnected-(B1-PadVCC)") (class "Default")
      (node (ref "B1") (pin "VCC") (pinfunction "VCC_VCC") (pintype "bidirectional"))
    )
    (net (code "104") (name "unconnected-(B1-PadVIN)") (class "Default")
      (node (ref "B1") (pin "VIN") (pinfunction "VIN_VIN") (pintype "bidirectional"))
    )
    (net (code "105") (name "unconnected-(B1-~{RESET}-PadRESET@1)") (class "Default")
      (node (ref "B1") (pin "RESET@1") (pinfunction "~{RESET}_RESET@1") (pintype "bidirectional"))
    )
    (net (code "106") (name "unconnected-(B1-~{RESET}-PadRESET@2)") (class "Default")
      (node (ref "B1") (pin "RESET@2") (pinfunction "~{RESET}_RESET@2") (pintype "bidirectional"))
    )
    (net (code "107") (name "unconnected-(D1-IO1-Pad1)") (class "Default")
      (node (ref "D1") (pin "1") (pinfunction "IO1_1") (pintype "passive"))
    )
    (net (code "108") (name "unconnected-(D1-IO4-Pad6)") (class "Default")
      (node (ref "D1") (pin "6") (pinfunction "IO4_6") (pintype "passive"))
    )
    (net (code "109") (name "unconnected-(J1-RX1+-PadB11)") (class "Default")
      (node (ref "J1") (pin "B11") (pinfunction "RX1+_B11") (pintype "bidirectional"))
    )
    (net (code "110") (name "unconnected-(J1-RX1--PadB10)") (class "Default")
      (node (ref "J1") (pin "B10") (pinfunction "RX1-_B10") (pintype "bidirectional"))
    )
    (net (code "111") (name "unconnected-(J1-RX2+-PadA11)") (class "Default")
      (node (ref "J1") (pin "A11") (pinfunction "RX2+_A11") (pintype "bidirectional"))
    )
    (net (code "112") (name "unconnected-(J1-RX2--PadA10)") (class "Default")
      (node (ref "J1") (pin "A10") (pinfunction "RX2-_A10") (pintype "bidirectional"))
    )
    (net (code "113") (name "unconnected-(J1-SBU1-PadA8)") (class "Default")
      (node (ref "J1") (pin "A8") (pinfunction "SBU1_A8") (pintype "bidirectional"))
    )
    (net (code "114") (name "unconnected-(J1-SBU2-PadB8)") (class "Default")
      (node (ref "J1") (pin "B8") (pinfunction "SBU2_B8") (pintype "bidirectional"))
    )
    (net (code "115") (name "unconnected-(J1-TX1+-PadA2)") (class "Default")
      (node (ref "J1") (pin "A2") (pinfunction "TX1+_A2") (pintype "bidirectional"))
    )
    (net (code "116") (name "unconnected-(J1-TX1--PadA3)") (class "Default")
      (node (ref "J1") (pin "A3") (pinfunction "TX1-_A3") (pintype "bidirectional"))
    )
    (net (code "117") (name "unconnected-(J1-TX2+-PadB2)") (class "Default")
      (node (ref "J1") (pin "B2") (pinfunction "TX2+_B2") (pintype "bidirectional"))
    )
    (net (code "118") (name "unconnected-(J1-TX2--PadB3)") (class "Default")
      (node (ref "J1") (pin "B3") (pinfunction "TX2-_B3") (pintype "bidirectional"))
    )
    (net (code "119") (name "unconnected-(J2-Pad1)") (class "Default")
      (node (ref "J2") (pin "1") (pinfunction "1_1") (pintype "passive"))
    )
    (net (code "120") (name "unconnected-(J2-Pad2)") (class "Default")
      (node (ref "J2") (pin "2") (pinfunction "2_2") (pintype "passive"))
    )
    (net (code "121") (name "unconnected-(J2-Pad3)") (class "Default")
      (node (ref "J2") (pin "3") (pinfunction "3_3") (pintype "passive"))
    )
    (net (code "122") (name "unconnected-(J2-Pad4)") (class "Default")
      (node (ref "J2") (pin "4") (pinfunction "4_4") (pintype "passive"))
    )
    (net (code "123") (name "unconnected-(J2-Pad5)") (class "Default")
      (node (ref "J2") (pin "5") (pinfunction "5_5") (pintype "passive"))
    )
    (net (code "124") (name "unconnected-(J2-Pad6)") (class "Default")
      (node (ref "J2") (pin "6") (pinfunction "6_6") (pintype "passive"))
    )
    (net (code "125") (name "unconnected-(J2-Pad7)") (class "Default")
      (node (ref "J2") (pin "7") (pinfunction "7_7") (pintype "passive"))
    )
    (net (code "126") (name "unconnected-(J2-Pad8)") (class "Default")
      (node (ref "J2") (pin "8") (pinfunction "8_8") (pintype "passive"))
    )
    (net (code "127") (name "unconnected-(J2-Pad9)") (class "Default")
      (node (ref "J2") (pin "9") (pinfunction "9_9") (pintype "passive"))
    )
    (net (code "128") (name "unconnected-(J2-Pad10)") (class "Default")
      (node (ref "J2") (pin "10") (pinfunction "10_10") (pintype "passive"))
    )
    (net (code "129") (name "unconnected-(J2-Pad11)") (class "Default")
      (node (ref "J2") (pin "11") (pinfunction "11_11") (pintype "passive"))
    )
    (net (code "130") (name "unconnected-(J2-Pad12)") (class "Default")
      (node (ref "J2") (pin "12") (pinfunction "12_12") (pintype "passive"))
    )
    (net (code "131") (name "unconnected-(J2-Pad13)") (class "Default")
      (node (ref "J2") (pin "13") (pinfunction "13_13") (pintype "passive"))
    )
    (net (code "132") (name "unconnected-(J2-Pad14)") (class "Default")
      (node (ref "J2") (pin "14") (pinfunction "14_14") (pintype "passive"))
    )
    (net (code "133") (name "unconnected-(J2-Pad15)") (class "Default")
      (node (ref "J2") (pin "15") (pinfunction "15_15") (pintype "passive"))
    )
    (net (code "134") (name "unconnected-(J2-Pad16)") (class "Default")
      (node (ref "J2") (pin "16") (pinfunction "16_16") (pintype "passive"))
    )
    (net (code "135") (name "unconnected-(J2-Pad17)") (class "Default")
      (node (ref "J2") (pin "17") (pinfunction "17_17") (pintype "passive"))
    )
    (net (code "136") (name "unconnected-(J2-Pad18)") (class "Default")
      (node (ref "J2") (pin "18") (pinfunction "18_18") (pintype "passive"))
    )
    (net (code "137") (name "unconnected-(J2-Pad19)") (class "Default")
      (node (ref "J2") (pin "19") (pinfunction "19_19") (pintype "passive"))
    )
    (net (code "138") (name "unconnected-(J3-Pad1)") (class "Default")
      (node (ref "J3") (pin "1") (pinfunction "1_1") (pintype "passive"))
    )
    (net (code "139") (name "unconnected-(J3-Pad2)") (class "Default")
      (node (ref "J3") (pin "2") (pinfunction "2_2") (pintype "passive"))
    )
    (net (code "140") (name "unconnected-(J3-Pad3)") (class "Default")
      (node (ref "J3") (pin "3") (pinfunction "3_3") (pintype "passive"))
    )
    (net (code "141") (name "unconnected-(J3-Pad4)") (class "Default")
      (node (ref "J3") (pin "4") (pinfunction "4_4") (pintype "passive"))
    )
    (net (code "142") (name "unconnected-(J3-Pad5)") (class "Default")
      (node (ref "J3") (pin "5") (pinfunction "5_5") (pintype "passive"))
    )
    (net (code "143") (name "unconnected-(J3-Pad6)") (class "Default")
      (node (ref "J3") (pin "6") (pinfunction "6_6") (pintype "passive"))
    )
    (net (code "144") (name "unconnected-(J3-Pad7)") (class "Default")
      (node (ref "J3") (pin "7") (pinfunction "7_7") (pintype "passive"))
    )
    (net (code "145") (name "unconnected-(J3-Pad8)") (class "Default")
      (node (ref "J3") (pin "8") (pinfunction "8_8") (pintype "passive"))
    )
    (net (code "146") (name "unconnected-(J3-Pad9)") (class "Default")
      (node (ref "J3") (pin "9") (pinfunction "9_9") (pintype "passive"))
    )
    (net (code "147") (name "unconnected-(J3-Pad10)") (class "Default")
      (node (ref "J3") (pin "10") (pinfunction "10_10") (pintype "passive"))
    )
    (net (code "148") (name "unconnected-(J3-Pad11)") (class "Default")
      (node (ref "J3") (pin "11") (pinfunction "11_11") (pintype "passive"))
    )
    (net (code "149") (name "unconnected-(J3-Pad12)") (class "Default")
      (node (ref "J3") (pin "12") (pinfunction "12_12") (pintype "passive"))
    )
    (net (code "150") (name "unconnected-(J3-Pad13)") (class "Default")
      (node (ref "J3") (pin "13") (pinfunction "13_13") (pintype "passive"))
    )
    (net (code "151") (name "unconnected-(J3-Pad14)") (class "Default")
      (node (ref "J3") (pin "14") (pinfunction "14_14") (pintype "passive"))
    )
    (net (code "152") (name "unconnected-(J3-Pad15)") (class "Default")
      (node (ref "J3") (pin "15") (pinfunction "15_15") (pintype "passive"))
    )
    (net (code "153") (name "unconnected-(J3-Pad16)") (class "Default")
      (node (ref "J3") (pin "16") (pinfunction "16_16") (pintype "passive"))
    )
    (net (code "154") (name "unconnected-(J3-Pad17)") (class "Default")
      (node (ref "J3") (pin "17") (pinfunction "17_17") (pintype "passive"))
    )
    (net (code "155") (name "unconnected-(J3-Pad18)") (class "Default")
      (node (ref "J3") (pin "18") (pinfunction "18_18") (pintype "passive"))
    )
    (net (code "156") (name "unconnected-(J3-Pad19)") (class "Default")
      (node (ref "J3") (pin "19") (pinfunction "19_19") (pintype "passive"))
    )
    (net (code "157") (name "unconnected-(U1-CLK-Pad20)") (class "Default")
      (node (ref "U1") (pin "20") (pinfunction "CLK_20") (pintype "bidirectional"))
    )
    (net (code "158") (name "unconnected-(U1-CMD-Pad19)") (class "Default")
      (node (ref "U1") (pin "19") (pinfunction "CMD_19") (pintype "bidirectional"))
    )
    (net (code "159") (name "unconnected-(U1-IO2-Pad24)") (class "Default")
      (node (ref "U1") (pin "24") (pinfunction "IO2_24") (pintype "bidirectional"))
    )
    (net (code "160") (name "unconnected-(U1-IO4-Pad26)") (class "Default")
      (node (ref "U1") (pin "26") (pinfunction "IO4_26") (pintype "bidirectional"))
    )
    (net (code "161") (name "unconnected-(U1-IO12-Pad14)") (class "Default")
      (node (ref "U1") (pin "14") (pinfunction "IO12_14") (pintype "bidirectional"))
    )
    (net (code "162") (name "unconnected-(U1-IO13-Pad16)") (class "Default")
      (node (ref "U1") (pin "16") (pinfunction "IO13_16") (pintype "bidirectional"))
    )
    (net (code "163") (name "unconnected-(U1-IO15-Pad23)") (class "Default")
      (node (ref "U1") (pin "23") (pinfunction "IO15_23") (pintype "bidirectional"))
    )
    (net (code "164") (name "unconnected-(U1-IO16-Pad27)") (class "Default")
      (node (ref "U1") (pin "27") (pinfunction "IO16_27") (pintype "bidirectional"))
    )
    (net (code "165") (name "unconnected-(U1-IO17-Pad28)") (class "Default")
      (node (ref "U1") (pin "28") (pinfunction "IO17_28") (pintype "bidirectional"))
    )
    (net (code "166") (name "unconnected-(U1-IO19-Pad31)") (class "Default")
      (node (ref "U1") (pin "31") (pinfunction "IO19_31") (pintype "bidirectional"))
    )
    (net (code "167") (name "unconnected-(U1-IO25-Pad10)") (class "Default")
      (node (ref "U1") (pin "10") (pinfunction "IO25_10") (pintype "bidirectional"))
    )
    (net (code "168") (name "unconnected-(U1-IO26-Pad11)") (class "Default")
      (node (ref "U1") (pin "11") (pinfunction "IO26_11") (pintype "bidirectional"))
    )
    (net (code "169") (name "unconnected-(U1-IO27-Pad12)") (class "Default")
      (node (ref "U1") (pin "12") (pinfunction "IO27_12") (pintype "bidirectional"))
    )
    (net (code "170") (name "unconnected-(U1-IO32-Pad8)") (class "Default")
      (node (ref "U1") (pin "8") (pinfunction "IO32_8") (pintype "bidirectional"))
    )
    (net (code "171") (name "unconnected-(U1-IO34-Pad6)") (class "Default")
      (node (ref "U1") (pin "6") (pinfunction "IO34_6") (pintype "bidirectional"))
    )
    (net (code "172") (name "unconnected-(U1-IO35-Pad7)") (class "Default")
      (node (ref "U1") (pin "7") (pinfunction "IO35_7") (pintype "bidirectional"))
    )
    (net (code "173") (name "unconnected-(U1-SD0-Pad21)") (class "Default")
      (node (ref "U1") (pin "21") (pinfunction "SD0_21") (pintype "bidirectional"))
    )
    (net (code "174") (name "unconnected-(U1-SD1-Pad22)") (class "Default")
      (node (ref "U1") (pin "22") (pinfunction "SD1_22") (pintype "bidirectional"))
    )
    (net (code "175") (name "unconnected-(U1-SD2-Pad17)") (class "Default")
      (node (ref "U1") (pin "17") (pinfunction "SD2_17") (pintype "bidirectional"))
    )
    (net (code "176") (name "unconnected-(U1-SD3-Pad18)") (class "Default")
      (node (ref "U1") (pin "18") (pinfunction "SD3_18") (pintype "bidirectional"))
    )
    (net (code "177") (name "unconnected-(U1-SVN-Pad5)") (class "Default")
      (node (ref "U1") (pin "5") (pinfunction "SVN_5") (pintype "bidirectional"))
    )
    (net (code "178") (name "unconnected-(U1-SVP-Pad4)") (class "Default")
      (node (ref "U1") (pin "4") (pinfunction "SVP_4") (pintype "bidirectional"))
    )
    (net (code "179") (name "unconnected-(U2A-PA02-Pad1)") (class "Default")
      (node (ref "U2") (pin "1") (pinfunction "PA02_1") (pintype "bidirectional"))
    )
    (net (code "180") (name "unconnected-(U2A-PA03-Pad2)") (class "Default")
      (node (ref "U2") (pin "2") (pinfunction "PA03_2") (pintype "bidirectional"))
    )
    (net (code "181") (name "unconnected-(U2A-PA04-Pad3)") (class "Default")
      (node (ref "U2") (pin "3") (pinfunction "PA04_3") (pintype "bidirectional"))
    )
    (net (code "182") (name "unconnected-(U2A-PA05-Pad4)") (class "Default")
      (node (ref "U2") (pin "4") (pinfunction "PA05_4") (pintype "bidirectional"))
    )
    (net (code "183") (name "unconnected-(U2A-PA06-Pad5)") (class "Default")
      (node (ref "U2") (pin "5") (pinfunction "PA06_5") (pintype "bidirectional"))
    )
    (net (code "184") (name "unconnected-(U2A-PA07-Pad6)") (class "Default")
      (node (ref "U2") (pin "6") (pinfunction "PA07_6") (pintype "bidirectional"))
    )
    (net (code "185") (name "unconnected-(U2A-PA08{slash}XIN32-Pad7)") (class "Default")
      (node (ref "U2") (pin "7") (pinfunction "PA08/XIN32_7") (pintype "bidirectional"))
    )
    (net (code "186") (name "unconnected-(U2A-PA09{slash}XOUT32-Pad8)") (class "Default")
      (node (ref "U2") (pin "8") (pinfunction "PA09/XOUT32_8") (pintype "bidirectional"))
    )
    (net (code "187") (name "unconnected-(U2A-PA10-Pad9)") (class "Default")
      (node (ref "U2") (pin "9") (pinfunction "PA10_9") (pintype "bidirectional"))
    )
    (net (code "188") (name "unconnected-(U2A-PA11-Pad10)") (class "Default")
      (node (ref "U2") (pin "10") (pinfunction "PA11_10") (pintype "bidirectional"))
    )
    (net (code "189") (name "unconnected-(U2A-PA16-Pad13)") (class "Default")
      (node (ref "U2") (pin "13") (pinfunction "PA16_13") (pintype "bidirectional"))
    )
    (net (code "190") (name "unconnected-(U2A-PA17-Pad14)") (class "Default")
      (node (ref "U2") (pin "14") (pinfunction "PA17_14") (pintype "bidirectional"))
    )
    (net (code "191") (name "unconnected-(U2A-PA27-Pad17)") (class "Default")
      (node (ref "U2") (pin "17") (pinfunction "PA27_17") (pintype "bidirectional"))
    )
    (net (code "192") (name "unconnected-(U6-1A-Pad3)") (class "Default")
      (node (ref "U6") (pin "3") (pinfunction "1A_3") (pintype "bidirectional"))
    )
    (net (code "193") (name "unconnected-(U6-1Y-Pad2)") (class "Default")
      (node (ref "U6") (pin "2") (pinfunction "1Y_2") (pintype "bidirectional"))
    )
    (net (code "194") (name "unconnected-(U6-4A-Pad9)") (class "Default")
      (node (ref "U6") (pin "9") (pinfunction "4A_9") (pintype "bidirectional"))
    )
    (net (code "195") (name "unconnected-(U6-4Y-Pad10)") (class "Default")
      (node (ref "U6") (pin "10") (pinfunction "4Y_10") (pintype "bidirectional"))
    )
  )
)
